# NeoDuino.net
KiCad netlist of a schematic drawn in EAGLE
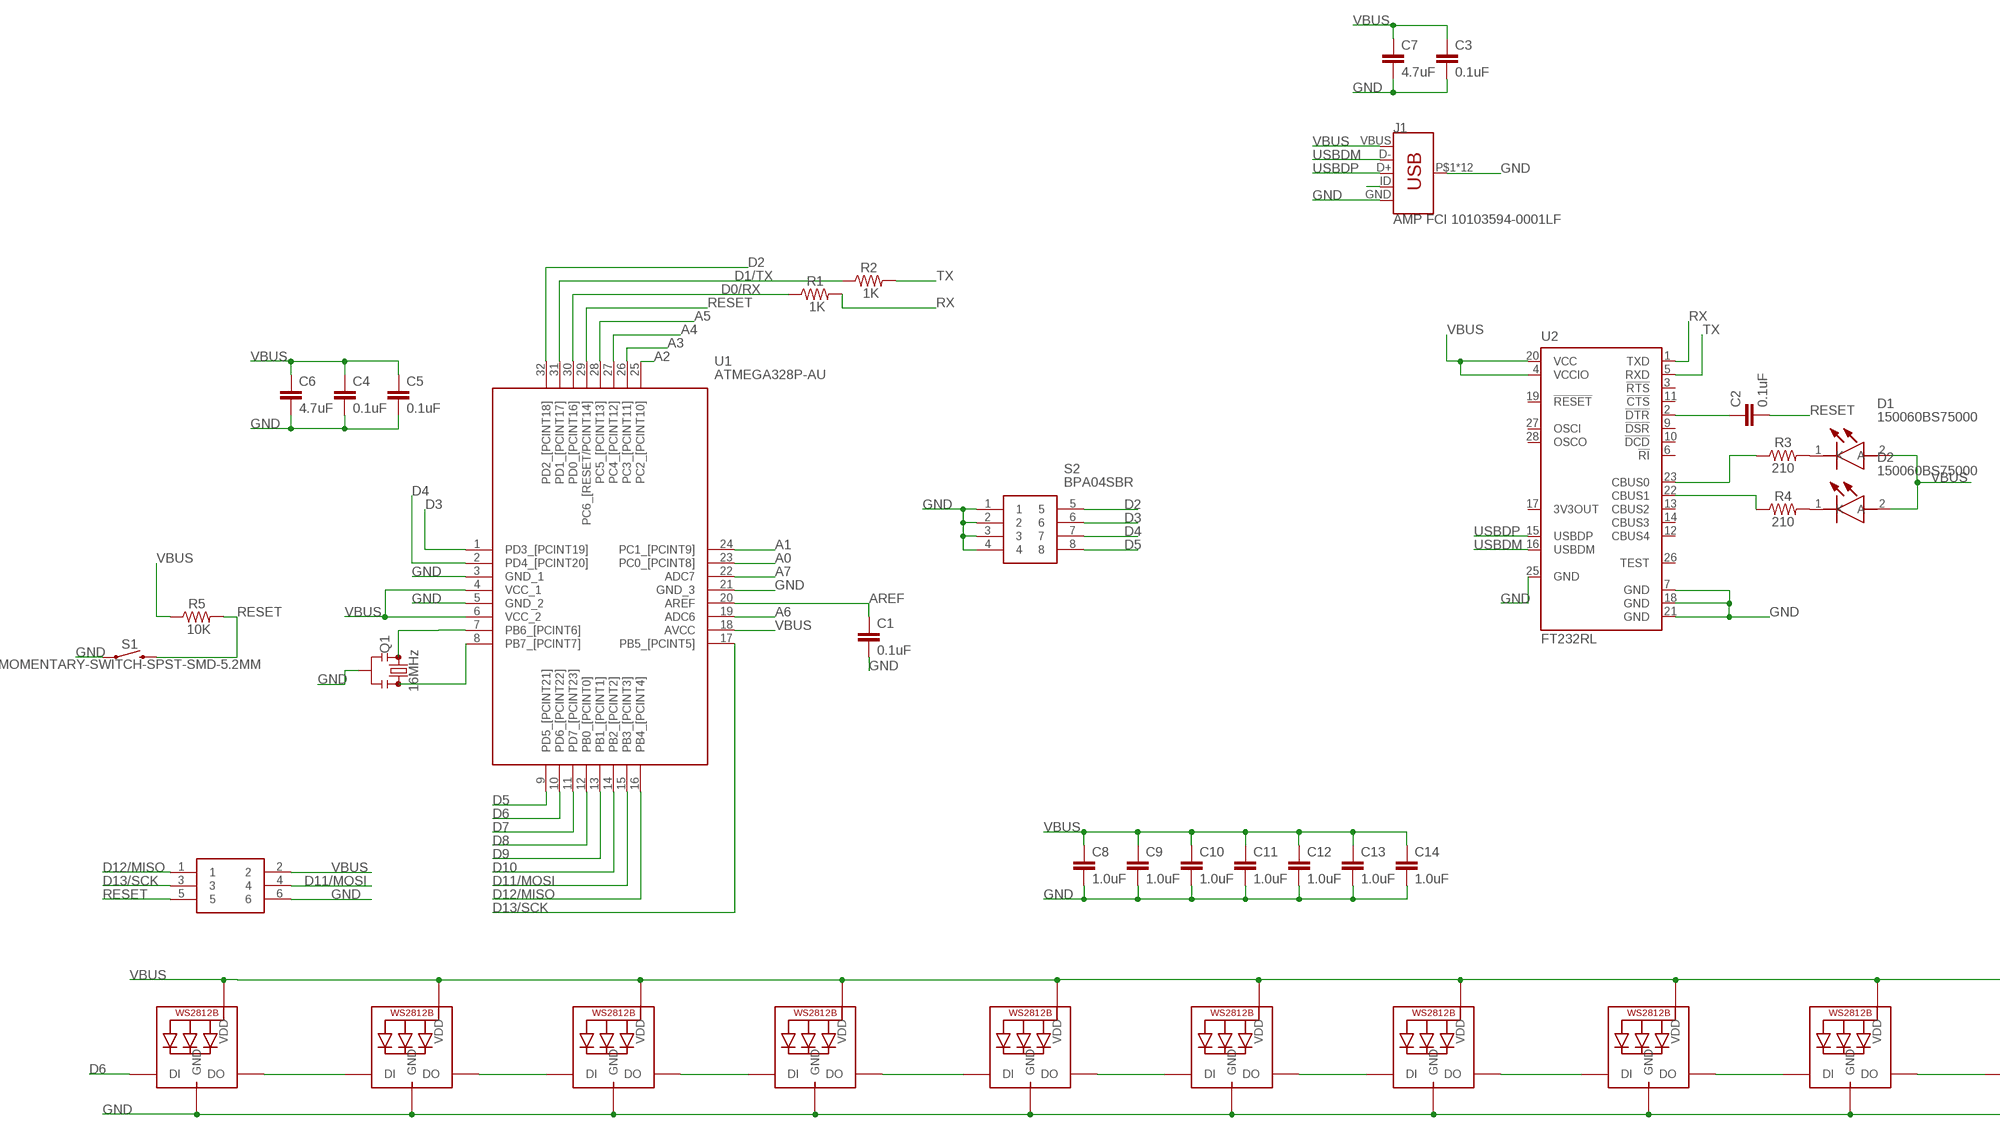
[diagram p0: schematic, sheet 1, part 1 of 2]
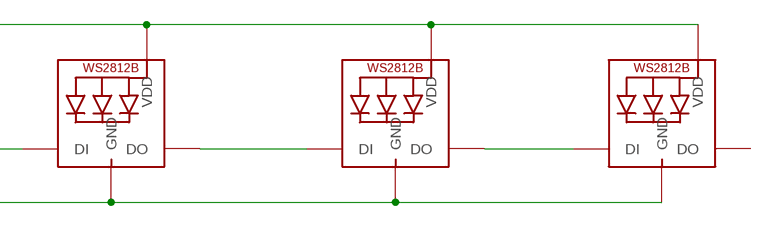
[diagram p1: schematic, sheet 1, part 2 of 2]

(export (version "E")
  (design (tool "Eeschema 10.0.6"))
  (components
    (comp (ref "C1")
      (value "0.1uF")
      (footprint "eagle-import:0402")
      (libsource (lib "eagle-import") (part "0.1UF-0402-16V-10%"))
    )
    (comp (ref "C2")
      (value "0.1uF")
      (footprint "eagle-import:0402")
      (libsource (lib "eagle-import") (part "0.1UF-0402-16V-10%"))
    )
    (comp (ref "C3")
      (value "0.1uF")
      (footprint "eagle-import:0402")
      (libsource (lib "eagle-import") (part "0.1UF-0402-16V-10%"))
    )
    (comp (ref "C4")
      (value "0.1uF")
      (footprint "eagle-import:0402")
      (libsource (lib "eagle-import") (part "0.1UF-0402-16V-10%"))
    )
    (comp (ref "C5")
      (value "0.1uF")
      (footprint "eagle-import:0402")
      (libsource (lib "eagle-import") (part "0.1UF-0402-16V-10%"))
    )
    (comp (ref "C6")
      (value "4.7uF")
      (footprint "eagle-import:0603")
      (libsource (lib "eagle-import") (part "4.7UF0603"))
    )
    (comp (ref "C7")
      (value "4.7uF")
      (footprint "eagle-import:0603")
      (libsource (lib "eagle-import") (part "4.7UF0603"))
    )
    (comp (ref "C8")
      (value "1.0uF")
      (footprint "eagle-import:0402")
      (libsource (lib "eagle-import") (part "1.0UF-0402-16V-10%"))
    )
    (comp (ref "C9")
      (value "1.0uF")
      (footprint "eagle-import:0402")
      (libsource (lib "eagle-import") (part "1.0UF-0402-16V-10%"))
    )
    (comp (ref "C10")
      (value "1.0uF")
      (footprint "eagle-import:0402")
      (libsource (lib "eagle-import") (part "1.0UF-0402-16V-10%"))
    )
    (comp (ref "C11")
      (value "1.0uF")
      (footprint "eagle-import:0402")
      (libsource (lib "eagle-import") (part "1.0UF-0402-16V-10%"))
    )
    (comp (ref "C12")
      (value "1.0uF")
      (footprint "eagle-import:0402")
      (libsource (lib "eagle-import") (part "1.0UF-0402-16V-10%"))
    )
    (comp (ref "C13")
      (value "1.0uF")
      (footprint "eagle-import:0402")
      (libsource (lib "eagle-import") (part "1.0UF-0402-16V-10%"))
    )
    (comp (ref "C14")
      (value "1.0uF")
      (footprint "eagle-import:0402")
      (libsource (lib "eagle-import") (part "1.0UF-0402-16V-10%"))
    )
    (comp (ref "D1")
      (value "150060BS75000")
      (footprint "eagle-import:LEDC1608X80N")
      (fields (field (name "RS_PART_NUMBER") "1623738"))
      (libsource (lib "eagle-import") (part "150060BS75000"))
    )
    (comp (ref "D2")
      (value "150060BS75000")
      (footprint "eagle-import:LEDC1608X80N")
      (fields (field (name "RS_PART_NUMBER") "1623738"))
      (libsource (lib "eagle-import") (part "150060BS75000"))
    )
    (comp (ref "D3")
      (value "WS2812B5050")
      (footprint "eagle-import:WS2812B")
      (libsource (lib "eagle-import") (part "WS2812B5050"))
    )
    (comp (ref "D4")
      (value "WS2812B5050")
      (footprint "eagle-import:WS2812B")
      (libsource (lib "eagle-import") (part "WS2812B5050"))
    )
    (comp (ref "D5")
      (value "WS2812B5050")
      (footprint "eagle-import:WS2812B")
      (libsource (lib "eagle-import") (part "WS2812B5050"))
    )
    (comp (ref "D6")
      (value "WS2812B5050")
      (footprint "eagle-import:WS2812B")
      (libsource (lib "eagle-import") (part "WS2812B5050"))
    )
    (comp (ref "D7")
      (value "WS2812B5050")
      (footprint "eagle-import:WS2812B")
      (libsource (lib "eagle-import") (part "WS2812B5050"))
    )
    (comp (ref "D8")
      (value "WS2812B5050")
      (footprint "eagle-import:WS2812B")
      (libsource (lib "eagle-import") (part "WS2812B5050"))
    )
    (comp (ref "D9")
      (value "WS2812B5050")
      (footprint "eagle-import:WS2812B")
      (libsource (lib "eagle-import") (part "WS2812B5050"))
    )
    (comp (ref "D10")
      (value "WS2812B5050")
      (footprint "eagle-import:WS2812B")
      (libsource (lib "eagle-import") (part "WS2812B5050"))
    )
    (comp (ref "D11")
      (value "WS2812B5050")
      (footprint "eagle-import:WS2812B")
      (libsource (lib "eagle-import") (part "WS2812B5050"))
    )
    (comp (ref "D12")
      (value "WS2812B5050")
      (footprint "eagle-import:WS2812B")
      (libsource (lib "eagle-import") (part "WS2812B5050"))
    )
    (comp (ref "D13")
      (value "WS2812B5050")
      (footprint "eagle-import:WS2812B")
      (libsource (lib "eagle-import") (part "WS2812B5050"))
    )
    (comp (ref "D14")
      (value "WS2812B5050")
      (footprint "eagle-import:WS2812B")
      (libsource (lib "eagle-import") (part "WS2812B5050"))
    )
    (comp (ref "J1")
      (value "AMP FCI 10103594-0001LF")
      (footprint "eagle-import:USB-MICROB-PTH")
      (libsource (lib "eagle-import") (part "USB_MICRO-B_HALF_PTH"))
    )
    (comp (ref "J2")
      (value "TSM-103-01-L-DH")
      (footprint "eagle-import:TSM-103-01-L-DH")
      (libsource (lib "eagle-import") (part "TSM-103-01-L-DH"))
    )
    (comp (ref "Q1")
      (value "16MHz")
      (footprint "eagle-import:RESONATOR-SMD-3.2X1.3")
      (libsource (lib "eagle-import") (part "RESONATOR-16MHZSMD_3.2X1.3"))
    )
    (comp (ref "R1")
      (value "1K")
      (footprint "eagle-import:0402")
      (libsource (lib "eagle-import") (part "RESISTOR0402"))
    )
    (comp (ref "R2")
      (value "1K")
      (footprint "eagle-import:0402")
      (libsource (lib "eagle-import") (part "RESISTOR0402"))
    )
    (comp (ref "R3")
      (value "210")
      (footprint "eagle-import:0402")
      (libsource (lib "eagle-import") (part "RESISTOR0402"))
    )
    (comp (ref "R4")
      (value "210")
      (footprint "eagle-import:0402")
      (libsource (lib "eagle-import") (part "RESISTOR0402"))
    )
    (comp (ref "R5")
      (value "10K")
      (footprint "eagle-import:0402")
      (libsource (lib "eagle-import") (part "RESISTOR0402"))
    )
    (comp (ref "S1")
      (value "MOMENTARY-SWITCH-SPST-SMD-5.2MM")
      (footprint "eagle-import:TACTILE_SWITCH_SMD_5.2MM")
      (libsource (lib "eagle-import") (part "MOMENTARY-SWITCH-SPST-SMD-5.2MM"))
    )
    (comp (ref "S2")
      (value "BPA04SBR")
      (footprint "eagle-import:BPA04SBR")
      (fields (field (name "RS_PART_NUMBER") "7931557P"))
      (libsource (lib "eagle-import") (part "BPA04SBR"))
    )
    (comp (ref "U1")
      (value "ATMEGA328P-AU")
      (footprint "eagle-import:QFP80P900X900X120-32N")
      (fields (field (name "RS_PART_NUMBER") "1310271"))
      (libsource (lib "eagle-import") (part "ATMEGA328P-AU"))
    )
    (comp (ref "U2")
      (value "FT232RL")
      (footprint "eagle-import:SSOP28")
      (libsource (lib "eagle-import") (part "FT232RL"))
    )
  )
  (nets
    (net (code "1") (name "/A0") (class "Default")
      (node (ref "U1") (pin "23") (pinfunction "PC0_[PCINT8]_23") (pintype "bidirectional"))
    )
    (net (code "2") (name "/A1") (class "Default")
      (node (ref "U1") (pin "24") (pinfunction "PC1_[PCINT9]_24") (pintype "bidirectional"))
    )
    (net (code "3") (name "/A2") (class "Default")
      (node (ref "U1") (pin "25") (pinfunction "PC2_[PCINT10]_25") (pintype "bidirectional"))
    )
    (net (code "4") (name "/A3") (class "Default")
      (node (ref "U1") (pin "26") (pinfunction "PC3_[PCINT11]_26") (pintype "bidirectional"))
    )
    (net (code "5") (name "/A4") (class "Default")
      (node (ref "U1") (pin "27") (pinfunction "PC4_[PCINT12]_27") (pintype "bidirectional"))
    )
    (net (code "6") (name "/A5") (class "Default")
      (node (ref "U1") (pin "28") (pinfunction "PC5_[PCINT13]_28") (pintype "bidirectional"))
    )
    (net (code "7") (name "/A6") (class "Default")
      (node (ref "U1") (pin "19") (pinfunction "ADC6_19") (pintype "bidirectional"))
    )
    (net (code "8") (name "/A7") (class "Default")
      (node (ref "U1") (pin "22") (pinfunction "ADC7_22") (pintype "bidirectional"))
    )
    (net (code "9") (name "/AREF") (class "Default")
      (node (ref "C1") (pin "1") (pinfunction "1_1") (pintype "passive"))
      (node (ref "U1") (pin "20") (pinfunction "AREF_20") (pintype "bidirectional"))
    )
    (net (code "10") (name "/D0{slash}RX") (class "Default")
      (node (ref "R1") (pin "1") (pinfunction "1_1") (pintype "passive"))
      (node (ref "U1") (pin "30") (pinfunction "PD0_[PCINT16]_30") (pintype "bidirectional"))
    )
    (net (code "11") (name "/D1{slash}TX") (class "Default")
      (node (ref "R2") (pin "1") (pinfunction "1_1") (pintype "passive"))
      (node (ref "U1") (pin "31") (pinfunction "PD1_[PCINT17]_31") (pintype "bidirectional"))
    )
    (net (code "12") (name "/D2") (class "Default")
      (node (ref "S2") (pin "5") (pinfunction "5_5") (pintype "bidirectional"))
      (node (ref "U1") (pin "32") (pinfunction "PD2_[PCINT18]_32") (pintype "bidirectional"))
    )
    (net (code "13") (name "/D3") (class "Default")
      (node (ref "S2") (pin "6") (pinfunction "6_6") (pintype "bidirectional"))
      (node (ref "U1") (pin "1") (pinfunction "PD3_[PCINT19]_1") (pintype "bidirectional"))
    )
    (net (code "14") (name "/D4") (class "Default")
      (node (ref "S2") (pin "7") (pinfunction "7_7") (pintype "bidirectional"))
      (node (ref "U1") (pin "2") (pinfunction "PD4_[PCINT20]_2") (pintype "bidirectional"))
    )
    (net (code "15") (name "/D5") (class "Default")
      (node (ref "S2") (pin "8") (pinfunction "8_8") (pintype "bidirectional"))
      (node (ref "U1") (pin "9") (pinfunction "PD5_[PCINT21]_9") (pintype "bidirectional"))
    )
    (net (code "16") (name "/D6") (class "Default")
      (node (ref "D3") (pin "4-DIN") (pinfunction "DI_4-DIN") (pintype "input"))
      (node (ref "U1") (pin "10") (pinfunction "PD6_[PCINT22]_10") (pintype "bidirectional"))
    )
    (net (code "17") (name "/D7") (class "Default")
      (node (ref "U1") (pin "11") (pinfunction "PD7_[PCINT23]_11") (pintype "bidirectional"))
    )
    (net (code "18") (name "/D8") (class "Default")
      (node (ref "U1") (pin "12") (pinfunction "PB0_[PCINT0]_12") (pintype "bidirectional"))
    )
    (net (code "19") (name "/D9") (class "Default")
      (node (ref "U1") (pin "13") (pinfunction "PB1_[PCINT1]_13") (pintype "bidirectional"))
    )
    (net (code "20") (name "/D10") (class "Default")
      (node (ref "U1") (pin "14") (pinfunction "PB2_[PCINT2]_14") (pintype "bidirectional"))
    )
    (net (code "21") (name "/D11{slash}MOSI") (class "Default")
      (node (ref "J2") (pin "4") (pinfunction "4_4") (pintype "bidirectional"))
      (node (ref "U1") (pin "15") (pinfunction "PB3_[PCINT3]_15") (pintype "bidirectional"))
    )
    (net (code "22") (name "/D12{slash}MISO") (class "Default")
      (node (ref "J2") (pin "1") (pinfunction "1_1") (pintype "bidirectional"))
      (node (ref "U1") (pin "16") (pinfunction "PB4_[PCINT4]_16") (pintype "bidirectional"))
    )
    (net (code "23") (name "/D13{slash}SCK") (class "Default")
      (node (ref "J2") (pin "3") (pinfunction "3_3") (pintype "bidirectional"))
      (node (ref "U1") (pin "17") (pinfunction "PB5_[PCINT5]_17") (pintype "bidirectional"))
    )
    (net (code "24") (name "/GND") (class "Default")
      (node (ref "C1") (pin "2") (pinfunction "2_2") (pintype "passive"))
      (node (ref "C10") (pin "2") (pinfunction "2_2") (pintype "passive"))
      (node (ref "C11") (pin "2") (pinfunction "2_2") (pintype "passive"))
      (node (ref "C12") (pin "2") (pinfunction "2_2") (pintype "passive"))
      (node (ref "C13") (pin "2") (pinfunction "2_2") (pintype "passive"))
      (node (ref "C14") (pin "2") (pinfunction "2_2") (pintype "passive"))
      (node (ref "C3") (pin "2") (pinfunction "2_2") (pintype "passive"))
      (node (ref "C4") (pin "2") (pinfunction "2_2") (pintype "passive"))
      (node (ref "C5") (pin "2") (pinfunction "2_2") (pintype "passive"))
      (node (ref "C6") (pin "2") (pinfunction "2_2") (pintype "passive"))
      (node (ref "C7") (pin "2") (pinfunction "2_2") (pintype "passive"))
      (node (ref "C8") (pin "2") (pinfunction "2_2") (pintype "passive"))
      (node (ref "C9") (pin "2") (pinfunction "2_2") (pintype "passive"))
      (node (ref "D10") (pin "3-GND") (pinfunction "GND_3-GND") (pintype "power_in"))
      (node (ref "D11") (pin "3-GND") (pinfunction "GND_3-GND") (pintype "power_in"))
      (node (ref "D12") (pin "3-GND") (pinfunction "GND_3-GND") (pintype "power_in"))
      (node (ref "D13") (pin "3-GND") (pinfunction "GND_3-GND") (pintype "power_in"))
      (node (ref "D14") (pin "3-GND") (pinfunction "GND_3-GND") (pintype "power_in"))
      (node (ref "D3") (pin "3-GND") (pinfunction "GND_3-GND") (pintype "power_in"))
      (node (ref "D4") (pin "3-GND") (pinfunction "GND_3-GND") (pintype "power_in"))
      (node (ref "D5") (pin "3-GND") (pinfunction "GND_3-GND") (pintype "power_in"))
      (node (ref "D6") (pin "3-GND") (pinfunction "GND_3-GND") (pintype "power_in"))
      (node (ref "D7") (pin "3-GND") (pinfunction "GND_3-GND") (pintype "power_in"))
      (node (ref "D8") (pin "3-GND") (pinfunction "GND_3-GND") (pintype "power_in"))
      (node (ref "D9") (pin "3-GND") (pinfunction "GND_3-GND") (pintype "power_in"))
      (node (ref "J1") (pin "GND") (pinfunction "GND_GND") (pintype "power_in"))
      (node (ref "J1") (pin "P$1") (pinfunction "SHIELD_P$1") (pintype "bidirectional"))
      (node (ref "J1") (pin "P$10") (pinfunction "SHIELD_P$10") (pintype "bidirectional"))
      (node (ref "J1") (pin "P$12") (pinfunction "SHIELD_P$12") (pintype "bidirectional"))
      (node (ref "J1") (pin "P$2") (pinfunction "SHIELD_P$2") (pintype "bidirectional"))
      (node (ref "J1") (pin "P$3") (pinfunction "SHIELD_P$3") (pintype "bidirectional"))
      (node (ref "J1") (pin "P$4") (pinfunction "SHIELD_P$4") (pintype "bidirectional"))
      (node (ref "J1") (pin "P$6") (pinfunction "SHIELD_P$6") (pintype "bidirectional"))
      (node (ref "J1") (pin "P$8") (pinfunction "SHIELD_P$8") (pintype "bidirectional"))
      (node (ref "J1") (pin "SHEILD2") (pinfunction "SHIELD_SHEILD2") (pintype "bidirectional"))
      (node (ref "J1") (pin "SHIELD") (pinfunction "SHIELD_SHIELD") (pintype "bidirectional"))
      (node (ref "J1") (pin "SHIELD3") (pinfunction "SHIELD_SHIELD3") (pintype "bidirectional"))
      (node (ref "J1") (pin "SHIELD4") (pinfunction "SHIELD_SHIELD4") (pintype "bidirectional"))
      (node (ref "J2") (pin "6") (pinfunction "6_6") (pintype "bidirectional"))
      (node (ref "Q1") (pin "2") (pinfunction "2_2") (pintype "passive"))
      (node (ref "S1") (pin "1") (pinfunction "1_1") (pintype "passive"))
      (node (ref "S2") (pin "1") (pinfunction "1_1") (pintype "bidirectional"))
      (node (ref "S2") (pin "2") (pinfunction "2_2") (pintype "bidirectional"))
      (node (ref "S2") (pin "3") (pinfunction "3_3") (pintype "bidirectional"))
      (node (ref "S2") (pin "4") (pinfunction "4_4") (pintype "bidirectional"))
      (node (ref "U1") (pin "21") (pinfunction "GND_3_21") (pintype "power_in"))
      (node (ref "U1") (pin "3") (pinfunction "GND_1_3") (pintype "power_in"))
      (node (ref "U1") (pin "5") (pinfunction "GND_2_5") (pintype "power_in"))
      (node (ref "U2") (pin "18") (pinfunction "GND_18") (pintype "power_in"))
      (node (ref "U2") (pin "21") (pinfunction "GND_21") (pintype "power_in"))
      (node (ref "U2") (pin "25") (pinfunction "GND_25") (pintype "power_in"))
      (node (ref "U2") (pin "7") (pinfunction "GND_7") (pintype "power_in"))
    )
    (net (code "25") (name "/RESET") (class "Default")
      (node (ref "C2") (pin "2") (pinfunction "2_2") (pintype "passive"))
      (node (ref "J2") (pin "5") (pinfunction "5_5") (pintype "bidirectional"))
      (node (ref "R5") (pin "2") (pinfunction "2_2") (pintype "passive"))
      (node (ref "S1") (pin "3") (pinfunction "2_3") (pintype "passive"))
      (node (ref "U1") (pin "29") (pinfunction "PC6_[RESET/PCINT14]_29") (pintype "bidirectional"))
    )
    (net (code "26") (name "/RX") (class "Default")
      (node (ref "R1") (pin "2") (pinfunction "2_2") (pintype "passive"))
      (node (ref "U2") (pin "1") (pinfunction "TXD_1") (pintype "output"))
    )
    (net (code "27") (name "/TX") (class "Default")
      (node (ref "R2") (pin "2") (pinfunction "2_2") (pintype "passive"))
      (node (ref "U2") (pin "5") (pinfunction "RXD_5") (pintype "input"))
    )
    (net (code "28") (name "/USBDM") (class "Default")
      (node (ref "J1") (pin "D-") (pinfunction "D-_D-") (pintype "bidirectional"))
      (node (ref "U2") (pin "16") (pinfunction "USBDM_16") (pintype "bidirectional"))
    )
    (net (code "29") (name "/USBDP") (class "Default")
      (node (ref "J1") (pin "D+") (pinfunction "D+_D+") (pintype "bidirectional"))
      (node (ref "U2") (pin "15") (pinfunction "USBDP_15") (pintype "bidirectional"))
    )
    (net (code "30") (name "/VBUS") (class "Default")
      (node (ref "C10") (pin "1") (pinfunction "1_1") (pintype "passive"))
      (node (ref "C11") (pin "1") (pinfunction "1_1") (pintype "passive"))
      (node (ref "C12") (pin "1") (pinfunction "1_1") (pintype "passive"))
      (node (ref "C13") (pin "1") (pinfunction "1_1") (pintype "passive"))
      (node (ref "C14") (pin "1") (pinfunction "1_1") (pintype "passive"))
      (node (ref "C3") (pin "1") (pinfunction "1_1") (pintype "passive"))
      (node (ref "C4") (pin "1") (pinfunction "1_1") (pintype "passive"))
      (node (ref "C5") (pin "1") (pinfunction "1_1") (pintype "passive"))
      (node (ref "C6") (pin "1") (pinfunction "1_1") (pintype "passive"))
      (node (ref "C7") (pin "1") (pinfunction "1_1") (pintype "passive"))
      (node (ref "C8") (pin "1") (pinfunction "1_1") (pintype "passive"))
      (node (ref "C9") (pin "1") (pinfunction "1_1") (pintype "passive"))
      (node (ref "D1") (pin "2") (pinfunction "A_2") (pintype "bidirectional"))
      (node (ref "D10") (pin "1-VDD") (pinfunction "VDD_1-VDD") (pintype "power_in"))
      (node (ref "D11") (pin "1-VDD") (pinfunction "VDD_1-VDD") (pintype "power_in"))
      (node (ref "D12") (pin "1-VDD") (pinfunction "VDD_1-VDD") (pintype "power_in"))
      (node (ref "D13") (pin "1-VDD") (pinfunction "VDD_1-VDD") (pintype "power_in"))
      (node (ref "D14") (pin "1-VDD") (pinfunction "VDD_1-VDD") (pintype "power_in"))
      (node (ref "D2") (pin "2") (pinfunction "A_2") (pintype "bidirectional"))
      (node (ref "D3") (pin "1-VDD") (pinfunction "VDD_1-VDD") (pintype "power_in"))
      (node (ref "D4") (pin "1-VDD") (pinfunction "VDD_1-VDD") (pintype "power_in"))
      (node (ref "D5") (pin "1-VDD") (pinfunction "VDD_1-VDD") (pintype "power_in"))
      (node (ref "D6") (pin "1-VDD") (pinfunction "VDD_1-VDD") (pintype "power_in"))
      (node (ref "D7") (pin "1-VDD") (pinfunction "VDD_1-VDD") (pintype "power_in"))
      (node (ref "D8") (pin "1-VDD") (pinfunction "VDD_1-VDD") (pintype "power_in"))
      (node (ref "D9") (pin "1-VDD") (pinfunction "VDD_1-VDD") (pintype "power_in"))
      (node (ref "J1") (pin "VBUS") (pinfunction "VBUS_VBUS") (pintype "power_in"))
      (node (ref "J2") (pin "2") (pinfunction "2_2") (pintype "bidirectional"))
      (node (ref "R5") (pin "1") (pinfunction "1_1") (pintype "passive"))
      (node (ref "U1") (pin "18") (pinfunction "AVCC_18") (pintype "power_in"))
      (node (ref "U1") (pin "4") (pinfunction "VCC_1_4") (pintype "power_in"))
      (node (ref "U1") (pin "6") (pinfunction "VCC_2_6") (pintype "power_in"))
      (node (ref "U2") (pin "20") (pinfunction "VCC_20") (pintype "power_in"))
      (node (ref "U2") (pin "4") (pinfunction "VCCIO_4") (pintype "power_in"))
    )
    (net (code "31") (name "Net-(D1-K)") (class "Default")
      (node (ref "D1") (pin "1") (pinfunction "K_1") (pintype "bidirectional"))
      (node (ref "R3") (pin "2") (pinfunction "2_2") (pintype "passive"))
    )
    (net (code "32") (name "Net-(D2-K)") (class "Default")
      (node (ref "D2") (pin "1") (pinfunction "K_1") (pintype "bidirectional"))
      (node (ref "R4") (pin "2") (pinfunction "2_2") (pintype "passive"))
    )
    (net (code "33") (name "Net-(D3-DO)") (class "Default")
      (node (ref "D3") (pin "2-DOUT") (pinfunction "DO_2-DOUT") (pintype "output"))
      (node (ref "D4") (pin "4-DIN") (pinfunction "DI_4-DIN") (pintype "input"))
    )
    (net (code "34") (name "Net-(D4-DO)") (class "Default")
      (node (ref "D4") (pin "2-DOUT") (pinfunction "DO_2-DOUT") (pintype "output"))
      (node (ref "D5") (pin "4-DIN") (pinfunction "DI_4-DIN") (pintype "input"))
    )
    (net (code "35") (name "Net-(D5-DO)") (class "Default")
      (node (ref "D5") (pin "2-DOUT") (pinfunction "DO_2-DOUT") (pintype "output"))
      (node (ref "D6") (pin "4-DIN") (pinfunction "DI_4-DIN") (pintype "input"))
    )
    (net (code "36") (name "Net-(D6-DO)") (class "Default")
      (node (ref "D6") (pin "2-DOUT") (pinfunction "DO_2-DOUT") (pintype "output"))
      (node (ref "D7") (pin "4-DIN") (pinfunction "DI_4-DIN") (pintype "input"))
    )
    (net (code "37") (name "Net-(D7-DO)") (class "Default")
      (node (ref "D7") (pin "2-DOUT") (pinfunction "DO_2-DOUT") (pintype "output"))
      (node (ref "D8") (pin "4-DIN") (pinfunction "DI_4-DIN") (pintype "input"))
    )
    (net (code "38") (name "Net-(D8-DO)") (class "Default")
      (node (ref "D8") (pin "2-DOUT") (pinfunction "DO_2-DOUT") (pintype "output"))
      (node (ref "D9") (pin "4-DIN") (pinfunction "DI_4-DIN") (pintype "input"))
    )
    (net (code "39") (name "Net-(D10-DI)") (class "Default")
      (node (ref "D10") (pin "4-DIN") (pinfunction "DI_4-DIN") (pintype "input"))
      (node (ref "D9") (pin "2-DOUT") (pinfunction "DO_2-DOUT") (pintype "output"))
    )
    (net (code "40") (name "Net-(D10-DO)") (class "Default")
      (node (ref "D10") (pin "2-DOUT") (pinfunction "DO_2-DOUT") (pintype "output"))
      (node (ref "D11") (pin "4-DIN") (pinfunction "DI_4-DIN") (pintype "input"))
    )
    (net (code "41") (name "Net-(D11-DO)") (class "Default")
      (node (ref "D11") (pin "2-DOUT") (pinfunction "DO_2-DOUT") (pintype "output"))
      (node (ref "D12") (pin "4-DIN") (pinfunction "DI_4-DIN") (pintype "input"))
    )
    (net (code "42") (name "Net-(D12-DO)") (class "Default")
      (node (ref "D12") (pin "2-DOUT") (pinfunction "DO_2-DOUT") (pintype "output"))
      (node (ref "D13") (pin "4-DIN") (pinfunction "DI_4-DIN") (pintype "input"))
    )
    (net (code "43") (name "Net-(D13-DO)") (class "Default")
      (node (ref "D13") (pin "2-DOUT") (pinfunction "DO_2-DOUT") (pintype "output"))
      (node (ref "D14") (pin "4-DIN") (pinfunction "DI_4-DIN") (pintype "input"))
    )
    (net (code "44") (name "Net-(U1-PB6_[PCINT6])") (class "Default")
      (node (ref "Q1") (pin "1") (pinfunction "1_1") (pintype "passive"))
      (node (ref "U1") (pin "7") (pinfunction "PB6_[PCINT6]_7") (pintype "bidirectional"))
    )
    (net (code "45") (name "Net-(U1-PB7_[PCINT7])") (class "Default")
      (node (ref "Q1") (pin "3") (pinfunction "3_3") (pintype "passive"))
      (node (ref "U1") (pin "8") (pinfunction "PB7_[PCINT7]_8") (pintype "bidirectional"))
    )
    (net (code "46") (name "Net-(U2-CBUS0)") (class "Default")
      (node (ref "R3") (pin "1") (pinfunction "1_1") (pintype "passive"))
      (node (ref "U2") (pin "23") (pinfunction "CBUS0_23") (pintype "bidirectional"))
    )
    (net (code "47") (name "Net-(U2-CBUS1)") (class "Default")
      (node (ref "R4") (pin "1") (pinfunction "1_1") (pintype "passive"))
      (node (ref "U2") (pin "22") (pinfunction "CBUS1_22") (pintype "bidirectional"))
    )
    (net (code "48") (name "Net-(U2-~{DTR})") (class "Default")
      (node (ref "C2") (pin "1") (pinfunction "1_1") (pintype "passive"))
      (node (ref "U2") (pin "2") (pinfunction "~{DTR}_2") (pintype "output"))
    )
    (net (code "49") (name "unconnected-(D14-DO-Pad2-DOUT)") (class "Default")
      (node (ref "D14") (pin "2-DOUT") (pinfunction "DO_2-DOUT") (pintype "output"))
    )
    (net (code "50") (name "unconnected-(J1-PadID)") (class "Default")
      (node (ref "J1") (pin "ID") (pinfunction "ID_ID") (pintype "bidirectional"))
    )
    (net (code "51") (name "unconnected-(U2-3V3OUT-Pad17)") (class "Default")
      (node (ref "U2") (pin "17") (pinfunction "3V3OUT_17") (pintype "output"))
    )
    (net (code "52") (name "unconnected-(U2-CBUS2-Pad13)") (class "Default")
      (node (ref "U2") (pin "13") (pinfunction "CBUS2_13") (pintype "bidirectional"))
    )
    (net (code "53") (name "unconnected-(U2-CBUS3-Pad14)") (class "Default")
      (node (ref "U2") (pin "14") (pinfunction "CBUS3_14") (pintype "bidirectional"))
    )
    (net (code "54") (name "unconnected-(U2-CBUS4-Pad12)") (class "Default")
      (node (ref "U2") (pin "12") (pinfunction "CBUS4_12") (pintype "bidirectional"))
    )
    (net (code "55") (name "unconnected-(U2-OSCI-Pad27)") (class "Default")
      (node (ref "U2") (pin "27") (pinfunction "OSCI_27") (pintype "input"))
    )
    (net (code "56") (name "unconnected-(U2-OSCO-Pad28)") (class "Default")
      (node (ref "U2") (pin "28") (pinfunction "OSCO_28") (pintype "output"))
    )
    (net (code "57") (name "unconnected-(U2-TEST-Pad26)") (class "Default")
      (node (ref "U2") (pin "26") (pinfunction "TEST_26") (pintype "input"))
    )
    (net (code "58") (name "unconnected-(U2-~{CTS}-Pad11)") (class "Default")
      (node (ref "U2") (pin "11") (pinfunction "~{CTS}_11") (pintype "input"))
    )
    (net (code "59") (name "unconnected-(U2-~{DCD}-Pad10)") (class "Default")
      (node (ref "U2") (pin "10") (pinfunction "~{DCD}_10") (pintype "input"))
    )
    (net (code "60") (name "unconnected-(U2-~{DSR}-Pad9)") (class "Default")
      (node (ref "U2") (pin "9") (pinfunction "~{DSR}_9") (pintype "input"))
    )
    (net (code "61") (name "unconnected-(U2-~{RESET}-Pad19)") (class "Default")
      (node (ref "U2") (pin "19") (pinfunction "~{RESET}_19") (pintype "input"))
    )
    (net (code "62") (name "unconnected-(U2-~{RI}-Pad6)") (class "Default")
      (node (ref "U2") (pin "6") (pinfunction "~{RI}_6") (pintype "input"))
    )
    (net (code "63") (name "unconnected-(U2-~{RTS}-Pad3)") (class "Default")
      (node (ref "U2") (pin "3") (pinfunction "~{RTS}_3") (pintype "output"))
    )
  )
)
